# 02A-003_Input_Switch.net
KiCad netlist of a schematic drawn in EAGLE
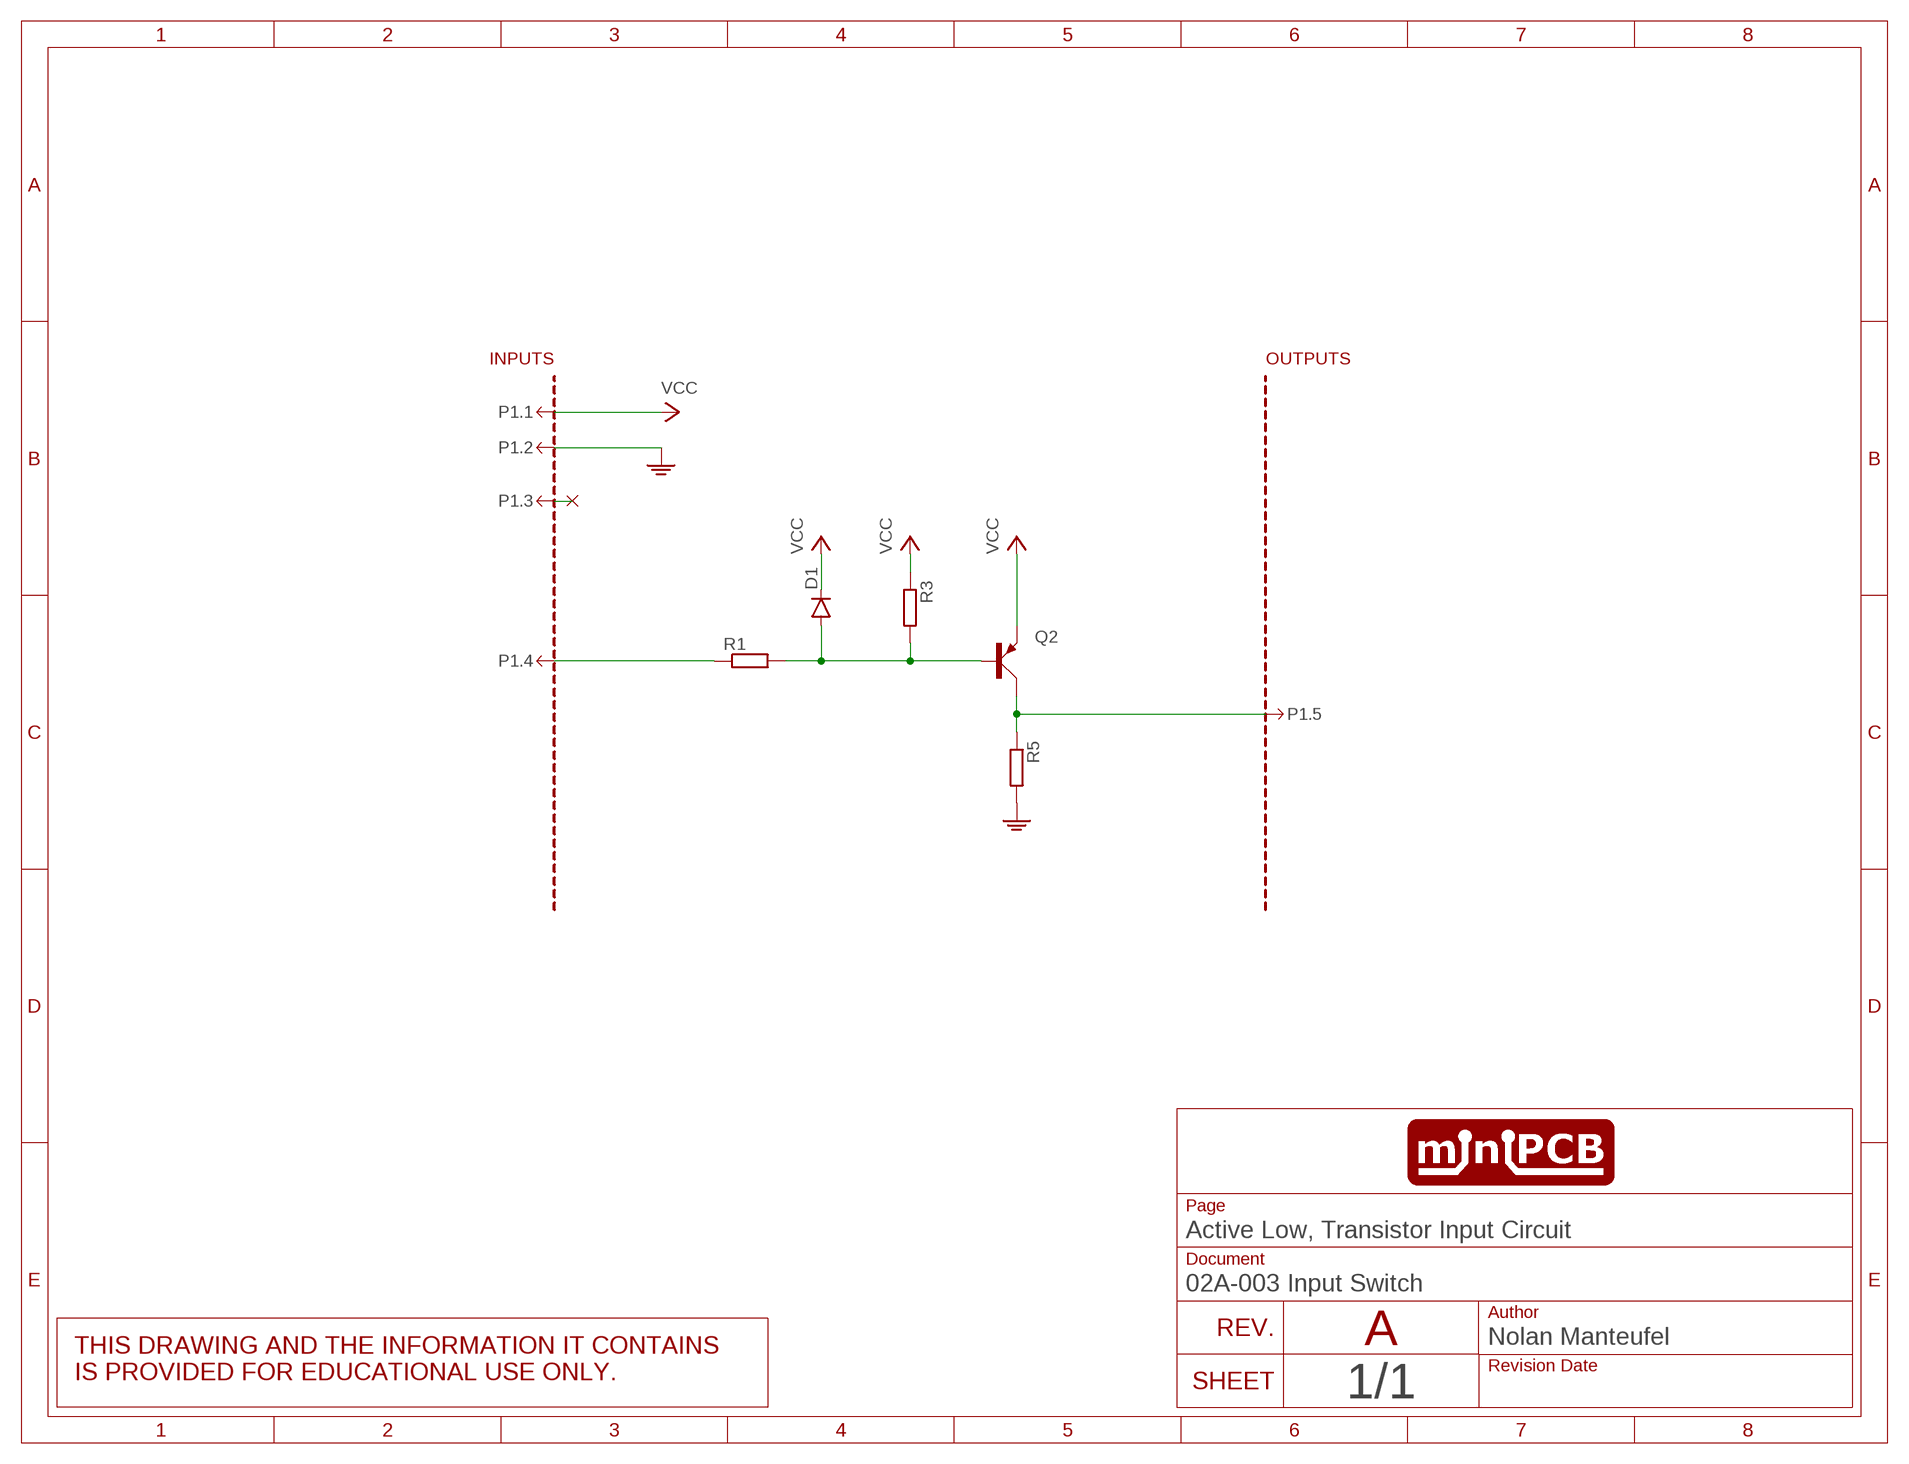
[diagram p0: schematic, sheet 1]

(export (version "E")
  (design (tool "Eeschema 10.0.6"))
  (components
    (comp (ref "D1")
      (value "DIODE-SOD80C")
      (footprint "eagle-import:SOD80C")
      (libsource (lib "eagle-import") (part "DIODE-SOD80C"))
    )
    (comp (ref "P1.")
      (value "MINIPCB_4INCH")
      (footprint "eagle-import:PCB_5")
      (libsource (lib "eagle-import") (part "MINIPCB_4INCH"))
    )
    (comp (ref "Q2")
      (value "BJT_PNPBEC")
      (footprint "eagle-import:SOT23")
      (libsource (lib "eagle-import") (part "BJT_PNPBEC"))
    )
    (comp (ref "R1")
      (value "R-EU_R0805")
      (footprint "eagle-import:R0805")
      (libsource (lib "eagle-import") (part "R-EU_R0805"))
    )
    (comp (ref "R3")
      (value "R-EU_R0805")
      (footprint "eagle-import:R0805")
      (libsource (lib "eagle-import") (part "R-EU_R0805"))
    )
    (comp (ref "R5")
      (value "R-EU_R0805")
      (footprint "eagle-import:R0805")
      (libsource (lib "eagle-import") (part "R-EU_R0805"))
    )
  )
  (nets
    (net (code "1") (name "GND") (class "Default")
      (node (ref "P1.") (pin "1") (pinfunction "1_1") (pintype "bidirectional"))
      (node (ref "R5") (pin "2") (pinfunction "2_2") (pintype "passive"))
    )
    (net (code "2") (name "Net-(P1.D-1)") (class "Default")
      (node (ref "P1.") (pin "4") (pinfunction "1_4") (pintype "bidirectional"))
      (node (ref "R1") (pin "1") (pinfunction "1_1") (pintype "passive"))
    )
    (net (code "3") (name "Net-(P1.E-1)") (class "Default")
      (node (ref "P1.") (pin "5") (pinfunction "1_5") (pintype "bidirectional"))
      (node (ref "Q2") (pin "3") (pinfunction "C_3") (pintype "passive"))
      (node (ref "R5") (pin "1") (pinfunction "1_1") (pintype "passive"))
    )
    (net (code "4") (name "Net-(Q2-B)") (class "Default")
      (node (ref "D1") (pin "A") (pinfunction "A_A") (pintype "passive"))
      (node (ref "Q2") (pin "1") (pinfunction "B_1") (pintype "passive"))
      (node (ref "R1") (pin "2") (pinfunction "2_2") (pintype "passive"))
      (node (ref "R3") (pin "2") (pinfunction "2_2") (pintype "passive"))
    )
    (net (code "5") (name "VCC") (class "Default")
      (node (ref "D1") (pin "C") (pinfunction "C_C") (pintype "passive"))
      (node (ref "P1.") (pin "2") (pinfunction "1_2") (pintype "bidirectional"))
      (node (ref "Q2") (pin "2") (pinfunction "E_2") (pintype "passive"))
      (node (ref "R3") (pin "1") (pinfunction "1_1") (pintype "passive"))
    )
    (net (code "6") (name "unconnected-(P1.C-1-Pad3)") (class "Default")
      (node (ref "P1.") (pin "3") (pinfunction "1_3") (pintype "bidirectional"))
    )
  )
)
